# CAN_node_rpm_f2v.net
KiCad netlist of a schematic drawn in EAGLE
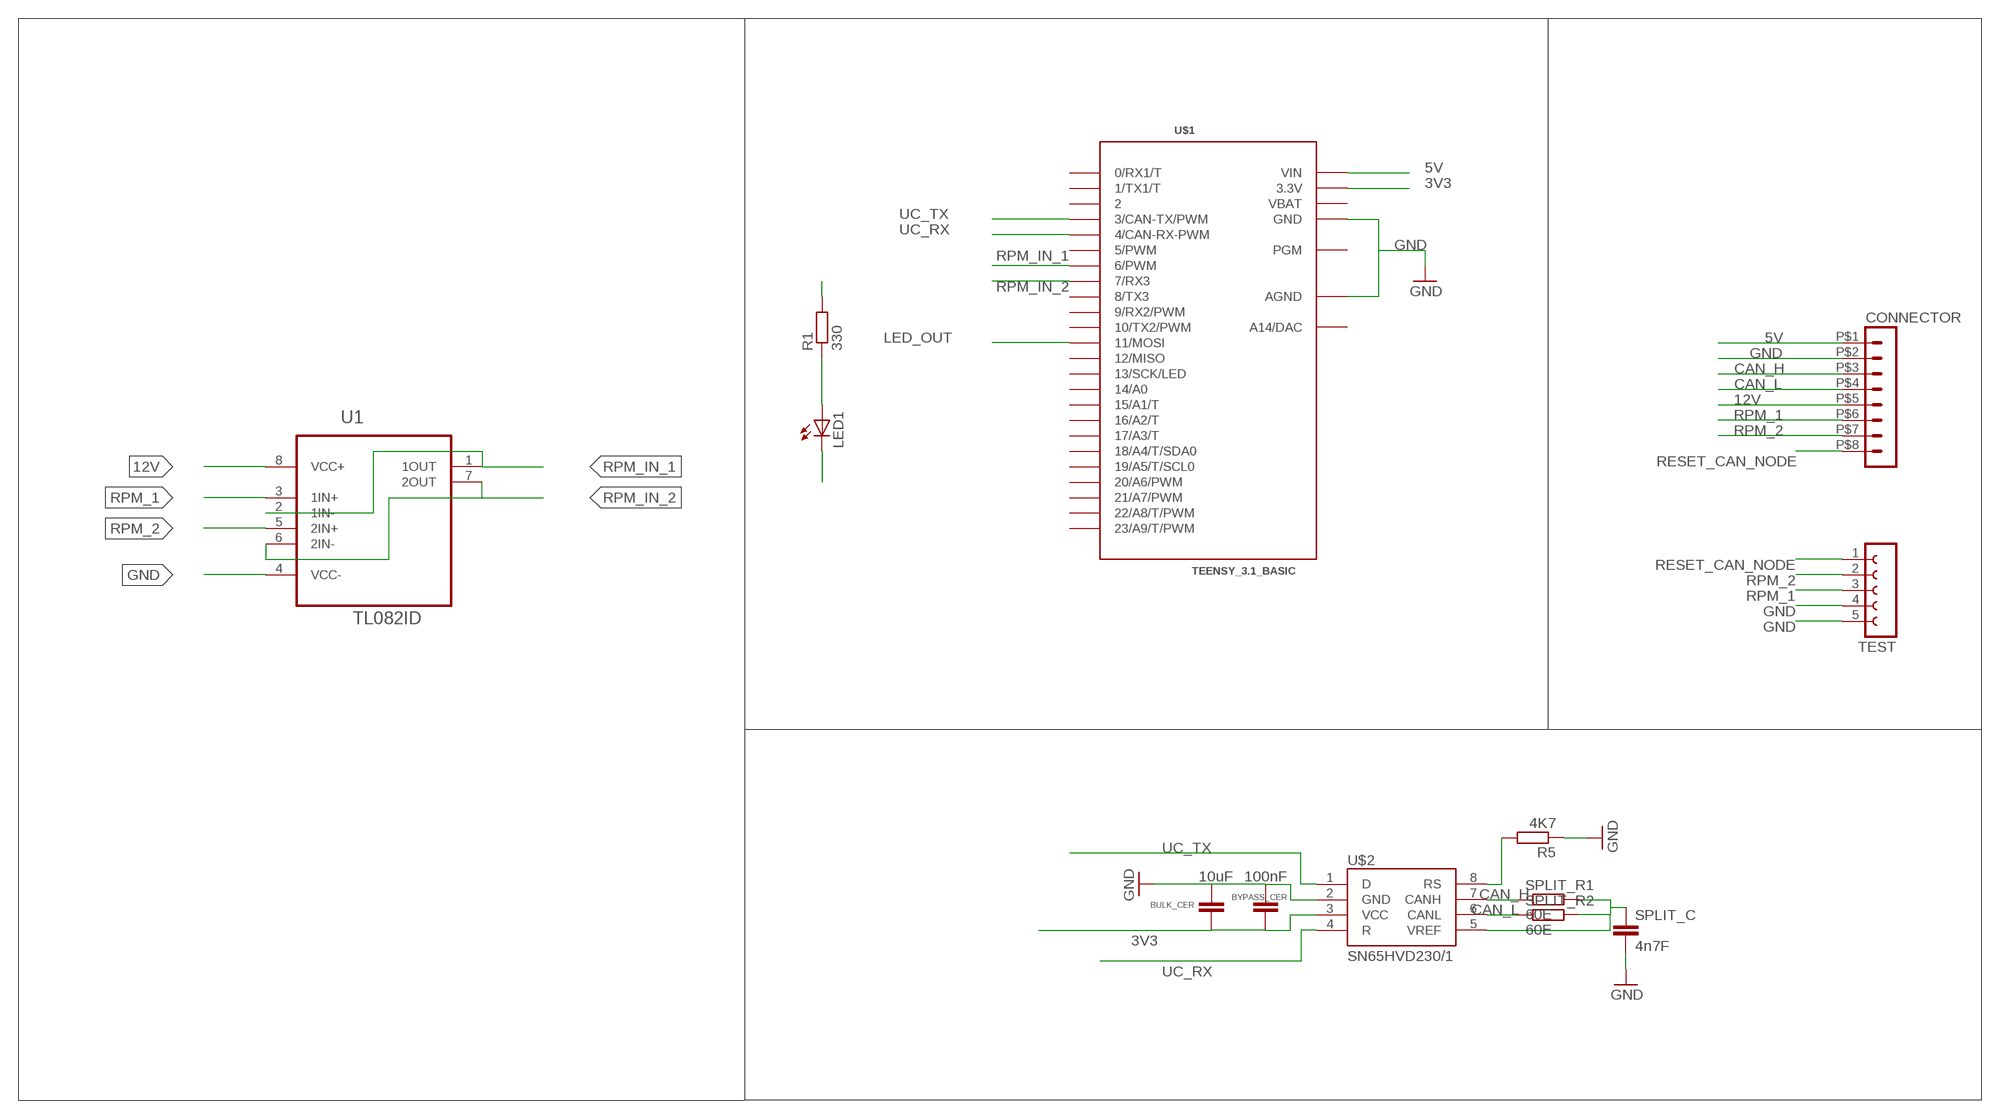
[diagram p0: schematic, sheet 1]

(export (version "E")
  (design (tool "Eeschema 10.0.6"))
  (components
    (comp (ref "BULK_CER")
      (value "10uF")
      (footprint "eagle-import:C0805")
      (libsource (lib "eagle-import") (part "C-EUC0805"))
    )
    (comp (ref "BYPASS_CER")
      (value "100nF")
      (footprint "eagle-import:C0805")
      (libsource (lib "eagle-import") (part "C-EUC0805"))
    )
    (comp (ref "CONNECTOR")
      (value "HEADER_POS8_43045-0812")
      (footprint "eagle-import:43045-0812")
      (libsource (lib "eagle-import") (part "HEADER_POS8_?43045-0812"))
    )
    (comp (ref "LED1")
      (value "LED_LEDSMT1206")
      (footprint "eagle-import:LED_1206")
      (libsource (lib "eagle-import") (part "LED_LEDSMT1206"))
    )
    (comp (ref "R1")
      (value "330")
      (footprint "eagle-import:R0805")
      (libsource (lib "eagle-import") (part "resistor_R-EU_R0805"))
    )
    (comp (ref "R5")
      (value "4K7")
      (footprint "eagle-import:R0805")
      (libsource (lib "eagle-import") (part "R-EU_R0805"))
    )
    (comp (ref "SPLIT_C")
      (value "4n7F")
      (footprint "eagle-import:C0805")
      (libsource (lib "eagle-import") (part "C-EUC0805"))
    )
    (comp (ref "SPLIT_R1")
      (value "60E")
      (footprint "eagle-import:R0805")
      (libsource (lib "eagle-import") (part "R-EU_R0805"))
    )
    (comp (ref "SPLIT_R2")
      (value "60E")
      (footprint "eagle-import:R0805")
      (libsource (lib "eagle-import") (part "R-EU_R0805"))
    )
    (comp (ref "TEST")
      (value "FE05-1")
      (footprint "eagle-import:FE05-1")
      (libsource (lib "eagle-import") (part "FE05-1"))
    )
    (comp (ref "U$1")
      (value "TEENSY_3.1_BASIC")
      (footprint "eagle-import:TEENSY_3.1_BASIC")
      (libsource (lib "eagle-import") (part "TEENSY_3.1_BASIC"))
    )
    (comp (ref "U$2")
      (value "SN65HVD230/1")
      (footprint "eagle-import:SO8")
      (libsource (lib "eagle-import") (part "SN65HVD230/1"))
    )
    (comp (ref "U1")
      (value "TL082ID")
      (footprint "eagle-import:SOIC127P600X175-8N")
      (libsource (lib "eagle-import") (part "TL082ID"))
    )
  )
  (nets
    (net (code "1") (name "/3V3") (class "Default")
      (node (ref "BULK_CER") (pin "1") (pinfunction "1_1") (pintype "passive"))
      (node (ref "BYPASS_CER") (pin "1") (pinfunction "1_1") (pintype "passive"))
      (node (ref "U$1") (pin "3.3V") (pinfunction "3.3V_3.3V") (pintype "power_in"))
      (node (ref "U$1") (pin "3.3V1") (pinfunction "3.3V_3.3V1") (pintype "power_in"))
      (node (ref "U$2") (pin "3") (pinfunction "VCC_3") (pintype "power_in"))
    )
    (net (code "2") (name "/5V") (class "Default")
      (node (ref "CONNECTOR") (pin "P$1") (pinfunction "1_P$1") (pintype "passive"))
      (node (ref "U$1") (pin "VIN") (pinfunction "VIN_VIN") (pintype "power_in"))
    )
    (net (code "3") (name "/CAN_H") (class "Default")
      (node (ref "CONNECTOR") (pin "P$3") (pinfunction "3_P$3") (pintype "passive"))
      (node (ref "SPLIT_R1") (pin "1") (pinfunction "1_1") (pintype "passive"))
      (node (ref "U$2") (pin "7") (pinfunction "CANH_7") (pintype "bidirectional"))
    )
    (net (code "4") (name "/CAN_L") (class "Default")
      (node (ref "CONNECTOR") (pin "P$4") (pinfunction "4_P$4") (pintype "passive"))
      (node (ref "SPLIT_R2") (pin "1") (pinfunction "1_1") (pintype "passive"))
      (node (ref "U$2") (pin "6") (pinfunction "CANL_6") (pintype "bidirectional"))
    )
    (net (code "5") (name "/LED_OUT") (class "Default")
      (node (ref "R1") (pin "2") (pinfunction "2_2") (pintype "passive"))
      (node (ref "U$1") (pin "11") (pinfunction "11/MOSI_11") (pintype "bidirectional"))
    )
    (net (code "6") (name "/RESET_CAN_NODE") (class "Default")
      (node (ref "CONNECTOR") (pin "P$8") (pinfunction "8_P$8") (pintype "passive"))
      (node (ref "TEST") (pin "1") (pinfunction "1_1") (pintype "passive"))
    )
    (net (code "7") (name "/UC_RX") (class "Default")
      (node (ref "U$1") (pin "4") (pinfunction "4/CAN-RX-PWM_4") (pintype "bidirectional"))
      (node (ref "U$2") (pin "4") (pinfunction "R_4") (pintype "bidirectional"))
    )
    (net (code "8") (name "/UC_TX") (class "Default")
      (node (ref "U$1") (pin "3") (pinfunction "3/CAN-TX/PWM_3") (pintype "bidirectional"))
      (node (ref "U$2") (pin "1") (pinfunction "D_1") (pintype "bidirectional"))
    )
    (net (code "9") (name "/VBAT") (class "Default")
      (node (ref "U$1") (pin "VBAT") (pinfunction "VBAT_VBAT") (pintype "power_in"))
    )
    (net (code "10") (name "12V") (class "Default")
      (node (ref "CONNECTOR") (pin "P$5") (pinfunction "5_P$5") (pintype "passive"))
      (node (ref "U1") (pin "8") (pinfunction "VCC+_8") (pintype "power_in"))
    )
    (net (code "11") (name "GND") (class "Default")
      (node (ref "BULK_CER") (pin "2") (pinfunction "2_2") (pintype "passive"))
      (node (ref "BYPASS_CER") (pin "2") (pinfunction "2_2") (pintype "passive"))
      (node (ref "CONNECTOR") (pin "P$2") (pinfunction "2_P$2") (pintype "passive"))
      (node (ref "LED1") (pin "C") (pinfunction "C_C") (pintype "passive"))
      (node (ref "R5") (pin "1") (pinfunction "1_1") (pintype "passive"))
      (node (ref "SPLIT_C") (pin "2") (pinfunction "2_2") (pintype "passive"))
      (node (ref "TEST") (pin "4") (pinfunction "4_4") (pintype "passive"))
      (node (ref "TEST") (pin "5") (pinfunction "5_5") (pintype "passive"))
      (node (ref "U$1") (pin "AGND") (pinfunction "AGND_AGND") (pintype "power_in"))
      (node (ref "U$1") (pin "GND") (pinfunction "GND_GND") (pintype "power_in"))
      (node (ref "U$1") (pin "GND1") (pinfunction "GND_GND1") (pintype "power_in"))
      (node (ref "U$2") (pin "2") (pinfunction "GND_2") (pintype "power_in"))
      (node (ref "U1") (pin "4") (pinfunction "VCC-_4") (pintype "passive"))
    )
    (net (code "12") (name "Net-(LED1-PadA)") (class "Default")
      (node (ref "LED1") (pin "A") (pinfunction "A_A") (pintype "passive"))
      (node (ref "R1") (pin "1") (pinfunction "1_1") (pintype "passive"))
    )
    (net (code "13") (name "Net-(U$2-RS)") (class "Default")
      (node (ref "R5") (pin "2") (pinfunction "2_2") (pintype "passive"))
      (node (ref "U$2") (pin "8") (pinfunction "RS_8") (pintype "bidirectional"))
    )
    (net (code "14") (name "Net-(U$2-VREF)") (class "Default")
      (node (ref "SPLIT_C") (pin "1") (pinfunction "1_1") (pintype "passive"))
      (node (ref "SPLIT_R1") (pin "2") (pinfunction "2_2") (pintype "passive"))
      (node (ref "SPLIT_R2") (pin "2") (pinfunction "2_2") (pintype "passive"))
      (node (ref "U$2") (pin "5") (pinfunction "VREF_5") (pintype "bidirectional"))
    )
    (net (code "15") (name "RPM_1") (class "Default")
      (node (ref "CONNECTOR") (pin "P$6") (pinfunction "6_P$6") (pintype "passive"))
      (node (ref "TEST") (pin "3") (pinfunction "3_3") (pintype "passive"))
      (node (ref "U1") (pin "3") (pinfunction "1IN+_3") (pintype "input"))
    )
    (net (code "16") (name "RPM_2") (class "Default")
      (node (ref "CONNECTOR") (pin "P$7") (pinfunction "7_P$7") (pintype "passive"))
      (node (ref "TEST") (pin "2") (pinfunction "2_2") (pintype "passive"))
      (node (ref "U1") (pin "5") (pinfunction "2IN+_5") (pintype "input"))
    )
    (net (code "17") (name "RPM_IN_1") (class "Default")
      (node (ref "U$1") (pin "6") (pinfunction "6/PWM_6") (pintype "bidirectional"))
      (node (ref "U1") (pin "1") (pinfunction "1OUT_1") (pintype "output"))
      (node (ref "U1") (pin "2") (pinfunction "1IN-_2") (pintype "input"))
    )
    (net (code "18") (name "RPM_IN_2") (class "Default")
      (node (ref "U$1") (pin "7") (pinfunction "7/RX3_7") (pintype "bidirectional"))
      (node (ref "U1") (pin "6") (pinfunction "2IN-_6") (pintype "input"))
      (node (ref "U1") (pin "7") (pinfunction "2OUT_7") (pintype "output"))
    )
    (net (code "19") (name "unconnected-(U$1-0{slash}RX1{slash}T-Pad0)") (class "Default")
      (node (ref "U$1") (pin "0") (pinfunction "0/RX1/T_0") (pintype "bidirectional"))
    )
    (net (code "20") (name "unconnected-(U$1-1{slash}TX1{slash}T-Pad1)") (class "Default")
      (node (ref "U$1") (pin "1") (pinfunction "1/TX1/T_1") (pintype "bidirectional"))
    )
    (net (code "21") (name "unconnected-(U$1-5{slash}PWM-Pad5)") (class "Default")
      (node (ref "U$1") (pin "5") (pinfunction "5/PWM_5") (pintype "bidirectional"))
    )
    (net (code "22") (name "unconnected-(U$1-8{slash}TX3-Pad8)") (class "Default")
      (node (ref "U$1") (pin "8") (pinfunction "8/TX3_8") (pintype "bidirectional"))
    )
    (net (code "23") (name "unconnected-(U$1-9{slash}RX2{slash}PWM-Pad9)") (class "Default")
      (node (ref "U$1") (pin "9") (pinfunction "9/RX2/PWM_9") (pintype "bidirectional"))
    )
    (net (code "24") (name "unconnected-(U$1-10{slash}TX2{slash}PWM-Pad10)") (class "Default")
      (node (ref "U$1") (pin "10") (pinfunction "10/TX2/PWM_10") (pintype "bidirectional"))
    )
    (net (code "25") (name "unconnected-(U$1-12{slash}MISO-Pad12)") (class "Default")
      (node (ref "U$1") (pin "12") (pinfunction "12/MISO_12") (pintype "bidirectional"))
    )
    (net (code "26") (name "unconnected-(U$1-13{slash}SCK{slash}LED-Pad13)") (class "Default")
      (node (ref "U$1") (pin "13") (pinfunction "13/SCK/LED_13") (pintype "bidirectional"))
    )
    (net (code "27") (name "unconnected-(U$1-15{slash}A1{slash}T-Pad15{slash}A1)") (class "Default")
      (node (ref "U$1") (pin "15/A1") (pinfunction "15/A1/T_15/A1") (pintype "bidirectional"))
    )
    (net (code "28") (name "unconnected-(U$1-16{slash}A2{slash}T-Pad16{slash}A2)") (class "Default")
      (node (ref "U$1") (pin "16/A2") (pinfunction "16/A2/T_16/A2") (pintype "bidirectional"))
    )
    (net (code "29") (name "unconnected-(U$1-17{slash}A3{slash}T-Pad17{slash}A3)") (class "Default")
      (node (ref "U$1") (pin "17/A3") (pinfunction "17/A3/T_17/A3") (pintype "bidirectional"))
    )
    (net (code "30") (name "unconnected-(U$1-18{slash}A4{slash}T{slash}SDA0-Pad18{slash}A4)") (class "Default")
      (node (ref "U$1") (pin "18/A4") (pinfunction "18/A4/T/SDA0_18/A4") (pintype "bidirectional"))
    )
    (net (code "31") (name "unconnected-(U$1-19{slash}A5{slash}T{slash}SCL0-Pad19{slash}A5)") (class "Default")
      (node (ref "U$1") (pin "19/A5") (pinfunction "19/A5/T/SCL0_19/A5") (pintype "bidirectional"))
    )
    (net (code "32") (name "unconnected-(U$1-20{slash}A6{slash}PWM-Pad20{slash}A6)") (class "Default")
      (node (ref "U$1") (pin "20/A6") (pinfunction "20/A6/PWM_20/A6") (pintype "bidirectional"))
    )
    (net (code "33") (name "unconnected-(U$1-21{slash}A7{slash}PWM-Pad21{slash}A7)") (class "Default")
      (node (ref "U$1") (pin "21/A7") (pinfunction "21/A7/PWM_21/A7") (pintype "bidirectional"))
    )
    (net (code "34") (name "unconnected-(U$1-22{slash}A8{slash}T{slash}PWM-Pad22{slash}A8)") (class "Default")
      (node (ref "U$1") (pin "22/A8") (pinfunction "22/A8/T/PWM_22/A8") (pintype "bidirectional"))
    )
    (net (code "35") (name "unconnected-(U$1-23{slash}A9{slash}T{slash}PWM-Pad23{slash}A9)") (class "Default")
      (node (ref "U$1") (pin "23/A9") (pinfunction "23/A9/T/PWM_23/A9") (pintype "bidirectional"))
    )
    (net (code "36") (name "unconnected-(U$1-A14{slash}DAC-PadA14)") (class "Default")
      (node (ref "U$1") (pin "A14") (pinfunction "A14/DAC_A14") (pintype "bidirectional"))
    )
    (net (code "37") (name "unconnected-(U$1-Pad2)") (class "Default")
      (node (ref "U$1") (pin "2") (pinfunction "2_2") (pintype "bidirectional"))
    )
    (net (code "38") (name "unconnected-(U$1-Pad14{slash}A0)") (class "Default")
      (node (ref "U$1") (pin "14/A0") (pinfunction "14/A0_14/A0") (pintype "bidirectional"))
    )
    (net (code "39") (name "unconnected-(U$1-PadPGM)") (class "Default")
      (node (ref "U$1") (pin "PGM") (pinfunction "PGM_PGM") (pintype "bidirectional"))
    )
  )
)
